# CapstoneProject16.net
KiCad netlist of a schematic drawn in EAGLE
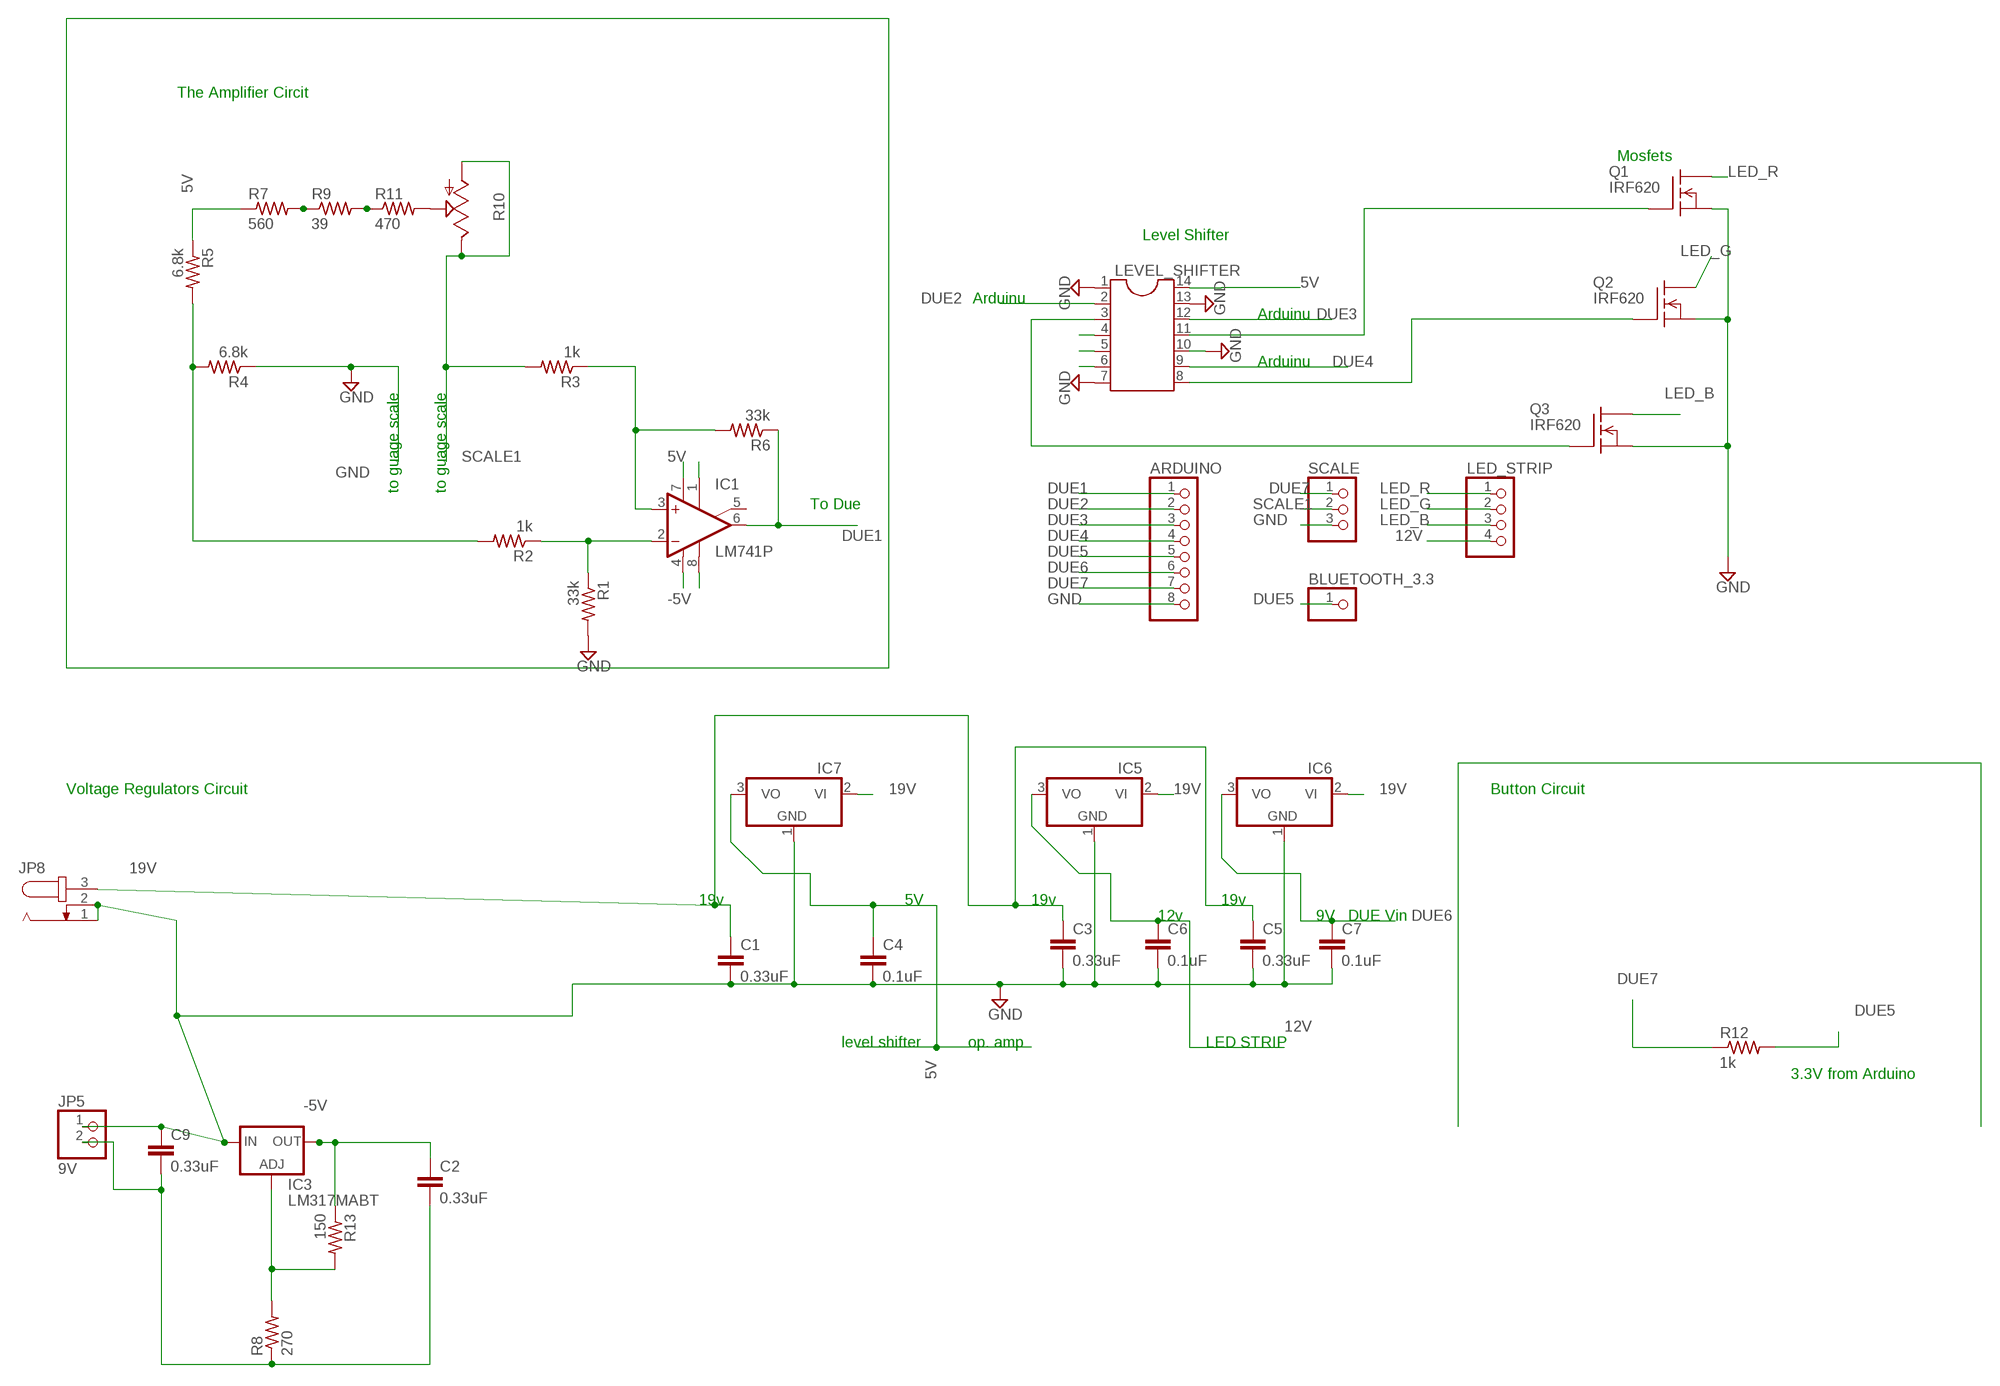
[diagram p0: schematic, sheet 1]

(export (version "E")
  (design (tool "Eeschema 10.0.6"))
  (components
    (comp (ref "ARDUINO")
      (value "PINHD-1X8")
      (footprint "eagle-import:1X08")
      (libsource (lib "eagle-import") (part "PINHD-1X8"))
    )
    (comp (ref "BLUETOOTH_3.3")
      (value "PINHD-1X1")
      (footprint "eagle-import:1X01")
      (libsource (lib "eagle-import") (part "PINHD-1X1"))
    )
    (comp (ref "C1")
      (value "0.33uF")
      (footprint "eagle-import:C2.5-3")
      (libsource (lib "eagle-import") (part "C2,5-3"))
    )
    (comp (ref "C2")
      (value "0.33uF")
      (footprint "eagle-import:C2.5-3")
      (libsource (lib "eagle-import") (part "C2,5-3"))
    )
    (comp (ref "C3")
      (value "0.33uF")
      (footprint "eagle-import:C2.5-3")
      (libsource (lib "eagle-import") (part "C2,5-3"))
    )
    (comp (ref "C4")
      (value "0.1uF")
      (footprint "eagle-import:C2.5-3")
      (libsource (lib "eagle-import") (part "C2,5-3"))
    )
    (comp (ref "C5")
      (value "0.33uF")
      (footprint "eagle-import:C2.5-3")
      (libsource (lib "eagle-import") (part "C2,5-3"))
    )
    (comp (ref "C6")
      (value "0.1uF")
      (footprint "eagle-import:C2.5-3")
      (libsource (lib "eagle-import") (part "C2,5-3"))
    )
    (comp (ref "C7")
      (value "0.1uF")
      (footprint "eagle-import:C2.5-3")
      (libsource (lib "eagle-import") (part "C2,5-3"))
    )
    (comp (ref "C9")
      (value "0.33uF")
      (footprint "eagle-import:C2.5-3")
      (libsource (lib "eagle-import") (part "C2,5-3"))
    )
    (comp (ref "IC1")
      (value "LM741P")
      (footprint "eagle-import:DIL08")
      (libsource (lib "eagle-import") (part "741PLM"))
    )
    (comp (ref "IC3")
      (value "LM317MABT")
      (footprint "eagle-import:TO220L1")
      (libsource (lib "eagle-import") (part "LM317?MABT"))
    )
    (comp (ref "IC5")
      (value "7905T")
      (footprint "eagle-import:TO220H")
      (libsource (lib "eagle-import") (part "79T05"))
    )
    (comp (ref "IC6")
      (value "7905T")
      (footprint "eagle-import:TO220H")
      (libsource (lib "eagle-import") (part "79T05"))
    )
    (comp (ref "IC7")
      (value "79L05Z")
      (footprint "eagle-import:TO92")
      (libsource (lib "eagle-import") (part "79ZL05"))
    )
    (comp (ref "JP5")
      (value "9V")
      (footprint "eagle-import:1X02")
      (libsource (lib "eagle-import") (part "PINHD-1X2"))
    )
    (comp (ref "JP8")
      (value "JACK-PLUG1")
      (footprint "eagle-import:SPC4078")
      (libsource (lib "eagle-import") (part "JACK-PLUG1"))
    )
    (comp (ref "LED_STRIP")
      (value "PINHD-1X4")
      (footprint "eagle-import:1X04")
      (libsource (lib "eagle-import") (part "PINHD-1X4"))
    )
    (comp (ref "LEVEL_SHIFTER")
      (value "DIL14")
      (footprint "eagle-import:DIL14")
      (libsource (lib "eagle-import") (part "DIL14"))
    )
    (comp (ref "Q1")
      (value "IRF620")
      (footprint "eagle-import:TO220")
      (libsource (lib "eagle-import") (part "IRF620"))
    )
    (comp (ref "Q2")
      (value "IRF620")
      (footprint "eagle-import:TO220")
      (libsource (lib "eagle-import") (part "IRF620"))
    )
    (comp (ref "Q3")
      (value "IRF620")
      (footprint "eagle-import:TO220")
      (libsource (lib "eagle-import") (part "IRF620"))
    )
    (comp (ref "R1")
      (value "33k")
      (footprint "eagle-import:0204_7")
      (libsource (lib "eagle-import") (part "R-US_0204/7"))
    )
    (comp (ref "R2")
      (value "1k")
      (footprint "eagle-import:0204_7")
      (libsource (lib "eagle-import") (part "R-US_0204/7"))
    )
    (comp (ref "R3")
      (value "1k")
      (footprint "eagle-import:0204_7")
      (libsource (lib "eagle-import") (part "R-US_0204/7"))
    )
    (comp (ref "R4")
      (value "6.8k")
      (footprint "eagle-import:0204_7")
      (libsource (lib "eagle-import") (part "R-US_0204/7"))
    )
    (comp (ref "R5")
      (value "6.8k")
      (footprint "eagle-import:0204_7")
      (libsource (lib "eagle-import") (part "R-US_0204/7"))
    )
    (comp (ref "R6")
      (value "33k")
      (footprint "eagle-import:0204_7")
      (libsource (lib "eagle-import") (part "R-US_0204/7"))
    )
    (comp (ref "R7")
      (value "560")
      (footprint "eagle-import:0204_7")
      (libsource (lib "eagle-import") (part "R-US_0204/7"))
    )
    (comp (ref "R8")
      (value "270")
      (footprint "eagle-import:0204_7")
      (libsource (lib "eagle-import") (part "R-US_0204/7"))
    )
    (comp (ref "R9")
      (value "39")
      (footprint "eagle-import:0204_7")
      (libsource (lib "eagle-import") (part "R-US_0204/7"))
    )
    (comp (ref "R10")
      (value "TRIM_US-S63P")
      (footprint "eagle-import:S63P")
      (libsource (lib "eagle-import") (part "TRIM_US-S63P"))
    )
    (comp (ref "R11")
      (value "470")
      (footprint "eagle-import:0204_7")
      (libsource (lib "eagle-import") (part "R-US_0204/7"))
    )
    (comp (ref "R12")
      (value "1k")
      (footprint "eagle-import:0204_7")
      (libsource (lib "eagle-import") (part "R-US_0204/7"))
    )
    (comp (ref "R13")
      (value "150")
      (footprint "eagle-import:0204_7")
      (libsource (lib "eagle-import") (part "R-US_0204/7"))
    )
    (comp (ref "SCALE")
      (value "PINHD-1X3")
      (footprint "eagle-import:1X03")
      (libsource (lib "eagle-import") (part "PINHD-1X3"))
    )
  )
  (nets
    (net (code "1") (name "/-5V") (class "Default")
      (node (ref "C2") (pin "1") (pinfunction "1_1") (pintype "passive"))
      (node (ref "IC1") (pin "4") (pinfunction "V-_4") (pintype "power_in"))
      (node (ref "IC3") (pin "2") (pinfunction "OUT_2") (pintype "passive"))
      (node (ref "R13") (pin "1") (pinfunction "1_1") (pintype "passive"))
    )
    (net (code "2") (name "/5V") (class "Default")
      (node (ref "C4") (pin "1") (pinfunction "1_1") (pintype "passive"))
      (node (ref "IC1") (pin "7") (pinfunction "V+_7") (pintype "power_in"))
      (node (ref "IC7") (pin "3") (pinfunction "VO_3") (pintype "passive"))
      (node (ref "LEVEL_SHIFTER") (pin "14") (pinfunction "14_14") (pintype "passive"))
      (node (ref "R5") (pin "1") (pinfunction "1_1") (pintype "passive"))
      (node (ref "R7") (pin "1") (pinfunction "1_1") (pintype "passive"))
    )
    (net (code "3") (name "/12V") (class "Default")
      (node (ref "C6") (pin "1") (pinfunction "1_1") (pintype "passive"))
      (node (ref "IC5") (pin "3") (pinfunction "VO_3") (pintype "passive"))
      (node (ref "LED_STRIP") (pin "4") (pinfunction "4_4") (pintype "passive"))
    )
    (net (code "4") (name "/19V") (class "Default")
      (node (ref "C1") (pin "1") (pinfunction "1_1") (pintype "passive"))
      (node (ref "C3") (pin "1") (pinfunction "1_1") (pintype "passive"))
      (node (ref "C5") (pin "1") (pinfunction "1_1") (pintype "passive"))
      (node (ref "IC5") (pin "2") (pinfunction "VI_2") (pintype "input"))
      (node (ref "IC6") (pin "2") (pinfunction "VI_2") (pintype "input"))
      (node (ref "IC7") (pin "2") (pinfunction "VI_2") (pintype "input"))
      (node (ref "JP8") (pin "3") (pinfunction "3_3") (pintype "passive"))
    )
    (net (code "5") (name "/DUE1") (class "Default")
      (node (ref "ARDUINO") (pin "1") (pinfunction "1_1") (pintype "passive"))
      (node (ref "IC1") (pin "6") (pinfunction "OUT_6") (pintype "output"))
      (node (ref "R6") (pin "1") (pinfunction "1_1") (pintype "passive"))
    )
    (net (code "6") (name "/DUE2") (class "Default")
      (node (ref "ARDUINO") (pin "2") (pinfunction "2_2") (pintype "passive"))
      (node (ref "LEVEL_SHIFTER") (pin "2") (pinfunction "2_2") (pintype "passive"))
    )
    (net (code "7") (name "/DUE3") (class "Default")
      (node (ref "ARDUINO") (pin "3") (pinfunction "3_3") (pintype "passive"))
      (node (ref "LEVEL_SHIFTER") (pin "12") (pinfunction "12_12") (pintype "passive"))
    )
    (net (code "8") (name "/DUE4") (class "Default")
      (node (ref "ARDUINO") (pin "4") (pinfunction "4_4") (pintype "passive"))
      (node (ref "LEVEL_SHIFTER") (pin "9") (pinfunction "9_9") (pintype "passive"))
    )
    (net (code "9") (name "/DUE5") (class "Default")
      (node (ref "ARDUINO") (pin "5") (pinfunction "5_5") (pintype "passive"))
      (node (ref "BLUETOOTH_3.3") (pin "1") (pinfunction "1_1") (pintype "passive"))
      (node (ref "R12") (pin "2") (pinfunction "2_2") (pintype "passive"))
    )
    (net (code "10") (name "/DUE6") (class "Default")
      (node (ref "ARDUINO") (pin "6") (pinfunction "6_6") (pintype "passive"))
      (node (ref "C7") (pin "1") (pinfunction "1_1") (pintype "passive"))
      (node (ref "IC6") (pin "3") (pinfunction "VO_3") (pintype "passive"))
    )
    (net (code "11") (name "/DUE7") (class "Default")
      (node (ref "ARDUINO") (pin "7") (pinfunction "7_7") (pintype "passive"))
      (node (ref "R12") (pin "1") (pinfunction "1_1") (pintype "passive"))
      (node (ref "SCALE") (pin "1") (pinfunction "1_1") (pintype "passive"))
    )
    (net (code "12") (name "/LED_B") (class "Default")
      (node (ref "LED_STRIP") (pin "3") (pinfunction "3_3") (pintype "passive"))
      (node (ref "Q3") (pin "2") (pinfunction "D_2") (pintype "passive"))
    )
    (net (code "13") (name "/LED_G") (class "Default")
      (node (ref "LED_STRIP") (pin "2") (pinfunction "2_2") (pintype "passive"))
      (node (ref "Q2") (pin "2") (pinfunction "D_2") (pintype "passive"))
    )
    (net (code "14") (name "/LED_R") (class "Default")
      (node (ref "LED_STRIP") (pin "1") (pinfunction "1_1") (pintype "passive"))
      (node (ref "Q1") (pin "2") (pinfunction "D_2") (pintype "passive"))
    )
    (net (code "15") (name "/SCALE1") (class "Default")
      (node (ref "R10") (pin "A") (pinfunction "A_A") (pintype "passive"))
      (node (ref "R10") (pin "E") (pinfunction "E_E") (pintype "passive"))
      (node (ref "R3") (pin "2") (pinfunction "2_2") (pintype "passive"))
      (node (ref "SCALE") (pin "2") (pinfunction "2_2") (pintype "passive"))
    )
    (net (code "16") (name "GND") (class "Default")
      (node (ref "ARDUINO") (pin "8") (pinfunction "8_8") (pintype "passive"))
      (node (ref "C1") (pin "2") (pinfunction "2_2") (pintype "passive"))
      (node (ref "C3") (pin "2") (pinfunction "2_2") (pintype "passive"))
      (node (ref "C4") (pin "2") (pinfunction "2_2") (pintype "passive"))
      (node (ref "C5") (pin "2") (pinfunction "2_2") (pintype "passive"))
      (node (ref "C6") (pin "2") (pinfunction "2_2") (pintype "passive"))
      (node (ref "C7") (pin "2") (pinfunction "2_2") (pintype "passive"))
      (node (ref "C9") (pin "1") (pinfunction "1_1") (pintype "passive"))
      (node (ref "IC3") (pin "3") (pinfunction "IN_3") (pintype "input"))
      (node (ref "IC5") (pin "1") (pinfunction "GND_1") (pintype "passive"))
      (node (ref "IC6") (pin "1") (pinfunction "GND_1") (pintype "passive"))
      (node (ref "IC7") (pin "1") (pinfunction "GND_1") (pintype "passive"))
      (node (ref "JP5") (pin "1") (pinfunction "1_1") (pintype "passive"))
      (node (ref "JP8") (pin "1") (pinfunction "1_1") (pintype "passive"))
      (node (ref "JP8") (pin "2") (pinfunction "2_2") (pintype "passive"))
      (node (ref "LEVEL_SHIFTER") (pin "1") (pinfunction "1_1") (pintype "passive"))
      (node (ref "LEVEL_SHIFTER") (pin "10") (pinfunction "10_10") (pintype "passive"))
      (node (ref "LEVEL_SHIFTER") (pin "13") (pinfunction "13_13") (pintype "passive"))
      (node (ref "LEVEL_SHIFTER") (pin "7") (pinfunction "7_7") (pintype "passive"))
      (node (ref "Q1") (pin "3") (pinfunction "S_3") (pintype "passive"))
      (node (ref "Q2") (pin "3") (pinfunction "S_3") (pintype "passive"))
      (node (ref "Q3") (pin "3") (pinfunction "S_3") (pintype "passive"))
      (node (ref "R1") (pin "2") (pinfunction "2_2") (pintype "passive"))
      (node (ref "R4") (pin "1") (pinfunction "1_1") (pintype "passive"))
      (node (ref "SCALE") (pin "3") (pinfunction "3_3") (pintype "passive"))
    )
    (net (code "17") (name "Net-(C2-Pad2)") (class "Default")
      (node (ref "C2") (pin "2") (pinfunction "2_2") (pintype "passive"))
      (node (ref "C9") (pin "2") (pinfunction "2_2") (pintype "passive"))
      (node (ref "JP5") (pin "2") (pinfunction "2_2") (pintype "passive"))
      (node (ref "R8") (pin "1") (pinfunction "1_1") (pintype "passive"))
    )
    (net (code "18") (name "Net-(IC1-+IN)") (class "Default")
      (node (ref "IC1") (pin "3") (pinfunction "+IN_3") (pintype "input"))
      (node (ref "R3") (pin "1") (pinfunction "1_1") (pintype "passive"))
      (node (ref "R6") (pin "2") (pinfunction "2_2") (pintype "passive"))
    )
    (net (code "19") (name "Net-(IC1--IN)") (class "Default")
      (node (ref "IC1") (pin "2") (pinfunction "-IN_2") (pintype "input"))
      (node (ref "R1") (pin "1") (pinfunction "1_1") (pintype "passive"))
      (node (ref "R2") (pin "1") (pinfunction "1_1") (pintype "passive"))
    )
    (net (code "20") (name "Net-(IC3-ADJ)") (class "Default")
      (node (ref "IC3") (pin "1") (pinfunction "ADJ_1") (pintype "input"))
      (node (ref "R13") (pin "2") (pinfunction "2_2") (pintype "passive"))
      (node (ref "R8") (pin "2") (pinfunction "2_2") (pintype "passive"))
    )
    (net (code "21") (name "Net-(Q1-G)") (class "Default")
      (node (ref "LEVEL_SHIFTER") (pin "11") (pinfunction "11_11") (pintype "passive"))
      (node (ref "Q1") (pin "1") (pinfunction "G_1") (pintype "passive"))
    )
    (net (code "22") (name "Net-(Q2-G)") (class "Default")
      (node (ref "LEVEL_SHIFTER") (pin "8") (pinfunction "8_8") (pintype "passive"))
      (node (ref "Q2") (pin "1") (pinfunction "G_1") (pintype "passive"))
    )
    (net (code "23") (name "Net-(Q3-G)") (class "Default")
      (node (ref "LEVEL_SHIFTER") (pin "3") (pinfunction "3_3") (pintype "passive"))
      (node (ref "Q3") (pin "1") (pinfunction "G_1") (pintype "passive"))
    )
    (net (code "24") (name "Net-(R2-Pad2)") (class "Default")
      (node (ref "R2") (pin "2") (pinfunction "2_2") (pintype "passive"))
      (node (ref "R4") (pin "2") (pinfunction "2_2") (pintype "passive"))
      (node (ref "R5") (pin "2") (pinfunction "2_2") (pintype "passive"))
    )
    (net (code "25") (name "Net-(R7-Pad2)") (class "Default")
      (node (ref "R7") (pin "2") (pinfunction "2_2") (pintype "passive"))
      (node (ref "R9") (pin "1") (pinfunction "1_1") (pintype "passive"))
    )
    (net (code "26") (name "Net-(R10-PadS)") (class "Default")
      (node (ref "R10") (pin "S") (pinfunction "S_S") (pintype "passive"))
      (node (ref "R11") (pin "2") (pinfunction "2_2") (pintype "passive"))
    )
    (net (code "27") (name "Net-(R11-Pad1)") (class "Default")
      (node (ref "R11") (pin "1") (pinfunction "1_1") (pintype "passive"))
      (node (ref "R9") (pin "2") (pinfunction "2_2") (pintype "passive"))
    )
    (net (code "28") (name "unconnected-(IC1-ON1-Pad1)") (class "Default")
      (node (ref "IC1") (pin "1") (pinfunction "ON1_1") (pintype "passive"))
    )
    (net (code "29") (name "unconnected-(IC1-ON2-Pad5)") (class "Default")
      (node (ref "IC1") (pin "5") (pinfunction "ON2_5") (pintype "passive"))
    )
    (net (code "30") (name "unconnected-(IC1-OPT-Pad8)") (class "Default")
      (node (ref "IC1") (pin "8") (pinfunction "OPT_8") (pintype "passive"))
    )
    (net (code "31") (name "unconnected-(LEVEL_SHIFTER-Pad4)") (class "Default")
      (node (ref "LEVEL_SHIFTER") (pin "4") (pinfunction "4_4") (pintype "passive"))
    )
    (net (code "32") (name "unconnected-(LEVEL_SHIFTER-Pad5)") (class "Default")
      (node (ref "LEVEL_SHIFTER") (pin "5") (pinfunction "5_5") (pintype "passive"))
    )
    (net (code "33") (name "unconnected-(LEVEL_SHIFTER-Pad6)") (class "Default")
      (node (ref "LEVEL_SHIFTER") (pin "6") (pinfunction "6_6") (pintype "passive"))
    )
  )
)
